# alarm_clock_devkit_esp32.net
KiCad netlist of a schematic drawn in Altium Designer
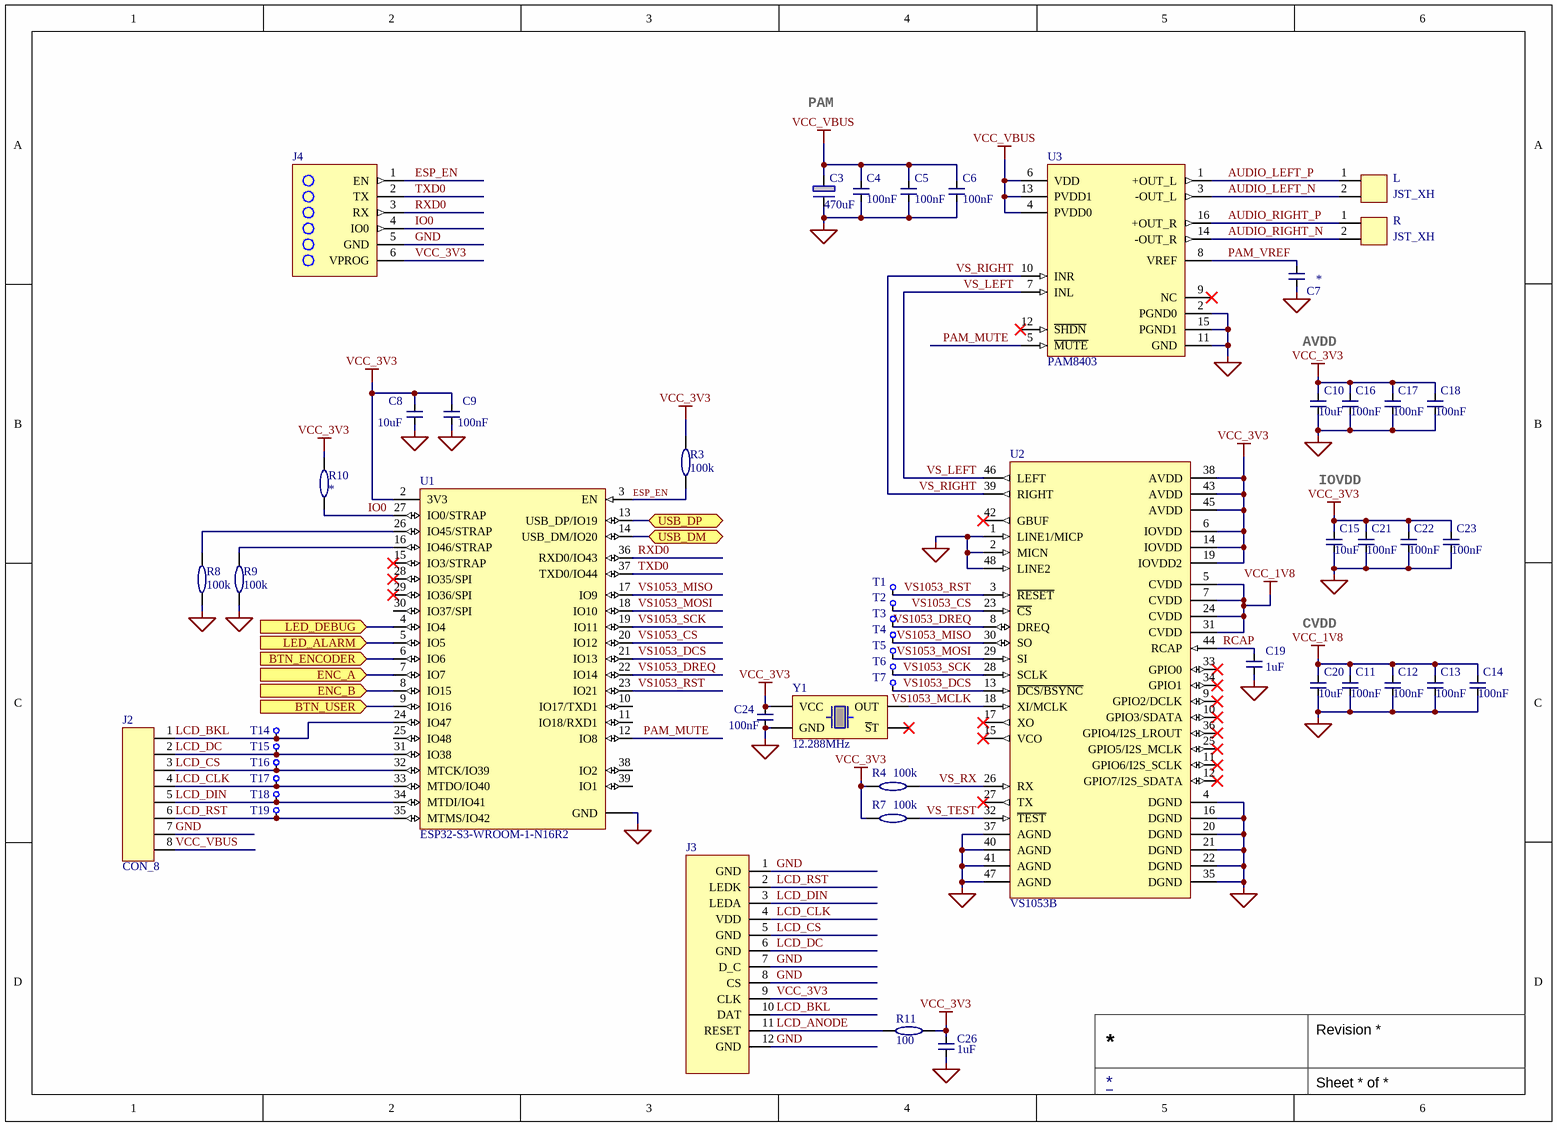
[diagram p0: alarm_clock_devkit_esp32.SchDoc]

(export (version "E")
  (design (tool "Eeschema 10.0.6"))
  (components
    (comp (ref "C3")
      (value "470uF")
      (footprint "CAPMP7343X11L")
      (description "Electrolytic Capacitor")
      (fields (field (name "MPN") "EEFCS1A470R") (field (name "VOLTAGE") "6.3V"))
      (libsource (lib "wifi_alarm_clock") (part "EEFCS1A470R"))
    )
    (comp (ref "C4")
      (value "100nF")
      (footprint "CAP 0603_1608")
      (description "MLCC")
      (libsource (lib "wifi_alarm_clock") (part "CAP_CERAMIC"))
    )
    (comp (ref "C5")
      (value "100nF")
      (footprint "CAP 0603_1608")
      (description "MLCC")
      (libsource (lib "wifi_alarm_clock") (part "CAP_CERAMIC"))
    )
    (comp (ref "C6")
      (value "100nF")
      (footprint "CAP 0603_1608")
      (description "MLCC")
      (libsource (lib "wifi_alarm_clock") (part "CAP_CERAMIC"))
    )
    (comp (ref "C7")
      (value "*")
      (footprint "CAP 0603_1608")
      (description "MLCC")
      (libsource (lib "wifi_alarm_clock") (part "CAP_CERAMIC"))
    )
    (comp (ref "C8")
      (value "10uF")
      (footprint "CAP 1210_3225")
      (description "MLCC")
      (libsource (lib "wifi_alarm_clock") (part "CAP_CERAMIC"))
    )
    (comp (ref "C9")
      (value "100nF")
      (footprint "CAP 0805_2012")
      (description "MLCC")
      (libsource (lib "wifi_alarm_clock") (part "CAP_CERAMIC"))
    )
    (comp (ref "C10")
      (value "10uF")
      (footprint "CAP 1210_3225")
      (description "MLCC")
      (libsource (lib "wifi_alarm_clock") (part "CAP_CERAMIC"))
    )
    (comp (ref "C11")
      (value "100nF")
      (footprint "CAP 0603_1608")
      (description "MLCC")
      (libsource (lib "wifi_alarm_clock") (part "CAP_CERAMIC"))
    )
    (comp (ref "C12")
      (value "100nF")
      (footprint "CAP 0603_1608")
      (description "MLCC")
      (libsource (lib "wifi_alarm_clock") (part "CAP_CERAMIC"))
    )
    (comp (ref "C13")
      (value "100nF")
      (footprint "CAP 0603_1608")
      (description "MLCC")
      (libsource (lib "wifi_alarm_clock") (part "CAP_CERAMIC"))
    )
    (comp (ref "C14")
      (value "100nF")
      (footprint "CAP 0603_1608")
      (description "MLCC")
      (libsource (lib "wifi_alarm_clock") (part "CAP_CERAMIC"))
    )
    (comp (ref "C15")
      (value "10uF")
      (footprint "CAP 1210_3225")
      (description "MLCC")
      (libsource (lib "wifi_alarm_clock") (part "CAP_CERAMIC"))
    )
    (comp (ref "C16")
      (value "100nF")
      (footprint "CAP 0603_1608")
      (description "MLCC")
      (libsource (lib "wifi_alarm_clock") (part "CAP_CERAMIC"))
    )
    (comp (ref "C17")
      (value "100nF")
      (footprint "CAP 0603_1608")
      (description "MLCC")
      (libsource (lib "wifi_alarm_clock") (part "CAP_CERAMIC"))
    )
    (comp (ref "C18")
      (value "100nF")
      (footprint "CAP 0603_1608")
      (description "MLCC")
      (libsource (lib "wifi_alarm_clock") (part "CAP_CERAMIC"))
    )
    (comp (ref "C19")
      (value "1uF")
      (footprint "CAP 0805_2012")
      (description "MLCC")
      (libsource (lib "wifi_alarm_clock") (part "CAP_CERAMIC"))
    )
    (comp (ref "C20")
      (value "10uF")
      (footprint "CAP 1210_3225")
      (description "MLCC")
      (libsource (lib "wifi_alarm_clock") (part "CAP_CERAMIC"))
    )
    (comp (ref "C21")
      (value "100nF")
      (footprint "CAP 0603_1608")
      (description "MLCC")
      (libsource (lib "wifi_alarm_clock") (part "CAP_CERAMIC"))
    )
    (comp (ref "C22")
      (value "100nF")
      (footprint "CAP 0603_1608")
      (description "MLCC")
      (libsource (lib "wifi_alarm_clock") (part "CAP_CERAMIC"))
    )
    (comp (ref "C23")
      (value "100nF")
      (footprint "CAP 0603_1608")
      (description "MLCC")
      (libsource (lib "wifi_alarm_clock") (part "CAP_CERAMIC"))
    )
    (comp (ref "C24")
      (value "100nF")
      (footprint "CAP 0603_1608")
      (description "MLCC")
      (libsource (lib "wifi_alarm_clock") (part "CAP_CERAMIC"))
    )
    (comp (ref "C26")
      (value "1uF")
      (footprint "CAP 0805_2012")
      (description "MLCC")
      (libsource (lib "wifi_alarm_clock") (part "CAP_CERAMIC"))
    )
    (comp (ref "J2") (value "CON_8") (footprint "CON8") (libsource (lib "wifi_alarm_clock") (part "CON_8")))
    (comp (ref "J3")
      (value "LCD_CON12")
      (footprint "LCD_CON12")
      (libsource (lib "wifi_alarm_clock") (part "LCD_CON12"))
    )
    (comp (ref "J4")
      (value "ESP_PROG")
      (footprint "ESP_PROG")
      (libsource (lib "wifi_alarm_clock") (part "ESP_PROG"))
    )
    (comp (ref "L")
      (value "JST_XH")
      (footprint "JST_XH_x2")
      (libsource (lib "wifi_alarm_clock") (part "JST_XH"))
    )
    (comp (ref "R")
      (value "JST_XH")
      (footprint "JST_XH_x2")
      (libsource (lib "wifi_alarm_clock") (part "JST_XH"))
    )
    (comp (ref "R3")
      (value "100k")
      (footprint "RES 0603_1608")
      (description "Resistor")
      (libsource (lib "wifi_alarm_clock") (part "RESISTOR"))
    )
    (comp (ref "R4")
      (value "100k")
      (footprint "RES 0603_1608")
      (description "Resistor")
      (libsource (lib "wifi_alarm_clock") (part "RESISTOR"))
    )
    (comp (ref "R7")
      (value "100k")
      (footprint "RES 0603_1608")
      (description "Resistor")
      (libsource (lib "wifi_alarm_clock") (part "RESISTOR"))
    )
    (comp (ref "R8")
      (value "100k")
      (footprint "RES 0603_1608")
      (description "Resistor")
      (libsource (lib "wifi_alarm_clock") (part "RESISTOR"))
    )
    (comp (ref "R9")
      (value "100k")
      (footprint "RES 0603_1608")
      (description "Resistor")
      (libsource (lib "wifi_alarm_clock") (part "RESISTOR"))
    )
    (comp (ref "R10")
      (value "*")
      (footprint "RES 0603_1608")
      (description "Resistor")
      (libsource (lib "wifi_alarm_clock") (part "RESISTOR"))
    )
    (comp (ref "R11")
      (value "100")
      (footprint "RES 0603_1608")
      (description "Resistor")
      (libsource (lib "wifi_alarm_clock") (part "RESISTOR"))
    )
    (comp (ref "T1")
      (value "TESTPOINT")
      (footprint "TESTPOINT_1MM")
      (libsource (lib "wifi_alarm_clock") (part "TESTPOINT"))
    )
    (comp (ref "T2")
      (value "TESTPOINT")
      (footprint "TESTPOINT_1MM")
      (libsource (lib "wifi_alarm_clock") (part "TESTPOINT"))
    )
    (comp (ref "T3")
      (value "TESTPOINT")
      (footprint "TESTPOINT_1MM")
      (libsource (lib "wifi_alarm_clock") (part "TESTPOINT"))
    )
    (comp (ref "T4")
      (value "TESTPOINT")
      (footprint "TESTPOINT_1MM")
      (libsource (lib "wifi_alarm_clock") (part "TESTPOINT"))
    )
    (comp (ref "T5")
      (value "TESTPOINT")
      (footprint "TESTPOINT_1MM")
      (libsource (lib "wifi_alarm_clock") (part "TESTPOINT"))
    )
    (comp (ref "T6")
      (value "TESTPOINT")
      (footprint "TESTPOINT_1MM")
      (libsource (lib "wifi_alarm_clock") (part "TESTPOINT"))
    )
    (comp (ref "T7")
      (value "TESTPOINT")
      (footprint "TESTPOINT_1MM")
      (libsource (lib "wifi_alarm_clock") (part "TESTPOINT"))
    )
    (comp (ref "T14")
      (value "TESTPOINT")
      (footprint "TESTPOINT_1MM")
      (libsource (lib "wifi_alarm_clock") (part "TESTPOINT"))
    )
    (comp (ref "T15")
      (value "TESTPOINT")
      (footprint "TESTPOINT_1MM")
      (libsource (lib "wifi_alarm_clock") (part "TESTPOINT"))
    )
    (comp (ref "T16")
      (value "TESTPOINT")
      (footprint "TESTPOINT_1MM")
      (libsource (lib "wifi_alarm_clock") (part "TESTPOINT"))
    )
    (comp (ref "T17")
      (value "TESTPOINT")
      (footprint "TESTPOINT_1MM")
      (libsource (lib "wifi_alarm_clock") (part "TESTPOINT"))
    )
    (comp (ref "T18")
      (value "TESTPOINT")
      (footprint "TESTPOINT_1MM")
      (libsource (lib "wifi_alarm_clock") (part "TESTPOINT"))
    )
    (comp (ref "T19")
      (value "TESTPOINT")
      (footprint "TESTPOINT_1MM")
      (libsource (lib "wifi_alarm_clock") (part "TESTPOINT"))
    )
    (comp (ref "U1")
      (value "ESP32-S3-WROOM-1-N16R2")
      (footprint "XCVR_ESP32-S3-WROOM-1-N16R2")
      (description "Bluetooth, WiFi 802.11b/g/n, Bluetooth v5.0 Transceiver Module 2.4GHz PCB Trace Surface Mount")
      (fields (field (name "MF") "Espressif Systems") (field (name "MP") "ESP32S3WROOM1N16R2"))
      (libsource (lib "wifi_alarm_clock") (part "ESP32-S3-WROOM-1-N16R2"))
    )
    (comp (ref "U2")
      (value "VS1053B")
      (footprint "CQFP50P900X900X140-48N")
      (description "VS1053B Music Maker Audio Feather Platform Evaluation Expansion Board")
      (fields (field (name "MF") "SparkFun Electronics"))
      (libsource (lib "wifi_alarm_clock") (part "VS1053B"))
    )
    (comp (ref "U3")
      (value "PAM8403")
      (footprint "SOIC127P600X175-16N")
      (description "Audio Amp Speaker 2-CH Stereo 3.2W Class-D 16-Pin SOP T/R")
      (fields (field (name "MF") "Diodes Zetex"))
      (libsource (lib "wifi_alarm_clock") (part "PAM8403"))
    )
    (comp (ref "Y1")
      (value "12.288MHz")
      (footprint "NDK NX3225GA")
      (description "SMT Crystal")
      (libsource (lib "wifi_alarm_clock") (part "OSCILLATOR"))
    )
  )
  (nets
    (net (code "1") (name "/AUDIO_LEFT_N") (class "Default")
      (node (ref "L") (pin "2") (pinfunction "2_2") (pintype "passive"))
      (node (ref "U3") (pin "3") (pinfunction "-OUT_L_3") (pintype "output"))
    )
    (net (code "2") (name "/AUDIO_LEFT_P") (class "Default")
      (node (ref "L") (pin "1") (pinfunction "1_1") (pintype "passive"))
      (node (ref "U3") (pin "1") (pinfunction "+OUT_L_1") (pintype "output"))
    )
    (net (code "3") (name "/AUDIO_RIGHT_N") (class "Default")
      (node (ref "R") (pin "2") (pinfunction "2_2") (pintype "passive"))
      (node (ref "U3") (pin "14") (pinfunction "-OUT_R_14") (pintype "output"))
    )
    (net (code "4") (name "/AUDIO_RIGHT_P") (class "Default")
      (node (ref "R") (pin "1") (pinfunction "1_1") (pintype "passive"))
      (node (ref "U3") (pin "16") (pinfunction "+OUT_R_16") (pintype "output"))
    )
    (net (code "5") (name "/BTN_ENCODER") (class "Default")
      (node (ref "U1") (pin "6") (pinfunction "IO6_6") (pintype "bidirectional"))
    )
    (net (code "6") (name "/BTN_USER") (class "Default")
      (node (ref "U1") (pin "9") (pinfunction "IO16_9") (pintype "bidirectional"))
    )
    (net (code "7") (name "/ENC_A") (class "Default")
      (node (ref "U1") (pin "7") (pinfunction "IO7_7") (pintype "bidirectional"))
    )
    (net (code "8") (name "/ENC_B") (class "Default")
      (node (ref "U1") (pin "8") (pinfunction "IO15_8") (pintype "bidirectional"))
    )
    (net (code "9") (name "/ESP_EN") (class "Default")
      (node (ref "J4") (pin "1") (pinfunction "EN_1") (pintype "output"))
      (node (ref "R3") (pin "1") (pinfunction "A_1") (pintype "passive"))
      (node (ref "U1") (pin "3") (pinfunction "EN_3") (pintype "input"))
    )
    (net (code "10") (name "/IO0") (class "Default")
      (node (ref "J4") (pin "4") (pinfunction "IO0_4") (pintype "output"))
      (node (ref "R10") (pin "2") (pinfunction "B_2") (pintype "passive"))
      (node (ref "U1") (pin "27") (pinfunction "IO0/STRAP_27") (pintype "bidirectional"))
    )
    (net (code "11") (name "/LCD_ANODE") (class "Default")
      (node (ref "J3") (pin "11") (pinfunction "RESET_11") (pintype "passive"))
      (node (ref "R11") (pin "1") (pinfunction "A_1") (pintype "passive"))
    )
    (net (code "12") (name "/LCD_BKL") (class "Default")
      (node (ref "J2") (pin "1") (pinfunction "1_1") (pintype "passive"))
      (node (ref "J3") (pin "10") (pinfunction "DAT_10") (pintype "passive"))
      (node (ref "T14") (pin "1") (pintype "passive"))
      (node (ref "U1") (pin "24") (pinfunction "IO47_24") (pintype "bidirectional"))
    )
    (net (code "13") (name "/LCD_CLK") (class "Default")
      (node (ref "J2") (pin "4") (pinfunction "4_4") (pintype "passive"))
      (node (ref "J3") (pin "4") (pinfunction "VDD_4") (pintype "passive"))
      (node (ref "T17") (pin "1") (pintype "passive"))
      (node (ref "U1") (pin "33") (pinfunction "MTDO/IO40_33") (pintype "bidirectional"))
    )
    (net (code "14") (name "/LCD_CS") (class "Default")
      (node (ref "J2") (pin "3") (pinfunction "3_3") (pintype "passive"))
      (node (ref "J3") (pin "5") (pinfunction "GND_5") (pintype "passive"))
      (node (ref "T16") (pin "1") (pintype "passive"))
      (node (ref "U1") (pin "32") (pinfunction "MTCK/IO39_32") (pintype "bidirectional"))
    )
    (net (code "15") (name "/LCD_DC") (class "Default")
      (node (ref "J2") (pin "2") (pinfunction "2_2") (pintype "passive"))
      (node (ref "J3") (pin "6") (pinfunction "GND_6") (pintype "passive"))
      (node (ref "T15") (pin "1") (pintype "passive"))
      (node (ref "U1") (pin "31") (pinfunction "IO38_31") (pintype "bidirectional"))
    )
    (net (code "16") (name "/LCD_DIN") (class "Default")
      (node (ref "J2") (pin "5") (pinfunction "5_5") (pintype "passive"))
      (node (ref "J3") (pin "3") (pinfunction "LEDA_3") (pintype "passive"))
      (node (ref "T18") (pin "1") (pintype "passive"))
      (node (ref "U1") (pin "34") (pinfunction "MTDI/IO41_34") (pintype "bidirectional"))
    )
    (net (code "17") (name "/LCD_RST") (class "Default")
      (node (ref "J2") (pin "6") (pinfunction "6_6") (pintype "passive"))
      (node (ref "J3") (pin "2") (pinfunction "LEDK_2") (pintype "passive"))
      (node (ref "T19") (pin "1") (pintype "passive"))
      (node (ref "U1") (pin "35") (pinfunction "MTMS/IO42_35") (pintype "bidirectional"))
    )
    (net (code "18") (name "/LED_ALARM") (class "Default")
      (node (ref "U1") (pin "5") (pinfunction "IO5_5") (pintype "bidirectional"))
    )
    (net (code "19") (name "/LED_DEBUG") (class "Default")
      (node (ref "U1") (pin "4") (pinfunction "IO4_4") (pintype "bidirectional"))
    )
    (net (code "20") (name "/PAM_MUTE") (class "Default")
      (node (ref "U1") (pin "12") (pinfunction "IO8_12") (pintype "bidirectional"))
      (node (ref "U3") (pin "5") (pinfunction "~{MUTE}_5") (pintype "input"))
    )
    (net (code "21") (name "/PAM_VREF") (class "Default")
      (node (ref "C7") (pin "2") (pinfunction "B_2") (pintype "passive"))
      (node (ref "U3") (pin "8") (pinfunction "VREF_8") (pintype "passive"))
    )
    (net (code "22") (name "/RCAP") (class "Default")
      (node (ref "C19") (pin "2") (pinfunction "B_2") (pintype "passive"))
      (node (ref "U2") (pin "44") (pinfunction "RCAP_44") (pintype "input"))
    )
    (net (code "23") (name "/RXD0") (class "Default")
      (node (ref "J4") (pin "3") (pinfunction "RX_3") (pintype "output"))
      (node (ref "U1") (pin "36") (pinfunction "RXD0/IO43_36") (pintype "bidirectional"))
    )
    (net (code "24") (name "/TXD0") (class "Default")
      (node (ref "J4") (pin "2") (pinfunction "TX_2") (pintype "passive"))
      (node (ref "U1") (pin "37") (pinfunction "TXD0/IO44_37") (pintype "bidirectional"))
    )
    (net (code "25") (name "/USB_DM") (class "Default")
      (node (ref "U1") (pin "14") (pinfunction "USB_DM/IO20_14") (pintype "bidirectional"))
    )
    (net (code "26") (name "/USB_DP") (class "Default")
      (node (ref "U1") (pin "13") (pinfunction "USB_DP/IO19_13") (pintype "bidirectional"))
    )
    (net (code "27") (name "/VS1053_CS") (class "Default")
      (node (ref "T2") (pin "1") (pintype "passive"))
      (node (ref "U1") (pin "20") (pinfunction "IO12_20") (pintype "bidirectional"))
      (node (ref "U2") (pin "23") (pinfunction "~{CS}_23") (pintype "input"))
    )
    (net (code "28") (name "/VS1053_DCS") (class "Default")
      (node (ref "T7") (pin "1") (pintype "passive"))
      (node (ref "U1") (pin "21") (pinfunction "IO13_21") (pintype "bidirectional"))
      (node (ref "U2") (pin "13") (pinfunction "~{DCS/BSYNC}_13") (pintype "input"))
    )
    (net (code "29") (name "/VS1053_DREQ") (class "Default")
      (node (ref "T3") (pin "1") (pintype "passive"))
      (node (ref "U1") (pin "22") (pinfunction "IO14_22") (pintype "bidirectional"))
      (node (ref "U2") (pin "8") (pinfunction "DREQ_8") (pintype "bidirectional"))
    )
    (net (code "30") (name "/VS1053_MCLK") (class "Default")
      (node (ref "U2") (pin "18") (pinfunction "XI/MCLK_18") (pintype "input"))
      (node (ref "Y1") (pin "3") (pinfunction "OUT_3") (pintype "passive"))
    )
    (net (code "31") (name "/VS1053_MISO") (class "Default")
      (node (ref "T4") (pin "1") (pintype "passive"))
      (node (ref "U1") (pin "17") (pinfunction "IO9_17") (pintype "bidirectional"))
      (node (ref "U2") (pin "30") (pinfunction "SO_30") (pintype "bidirectional"))
    )
    (net (code "32") (name "/VS1053_MOSI") (class "Default")
      (node (ref "T5") (pin "1") (pintype "passive"))
      (node (ref "U1") (pin "18") (pinfunction "IO10_18") (pintype "bidirectional"))
      (node (ref "U2") (pin "29") (pinfunction "SI_29") (pintype "input"))
    )
    (net (code "33") (name "/VS1053_RST") (class "Default")
      (node (ref "T1") (pin "1") (pintype "passive"))
      (node (ref "U1") (pin "23") (pinfunction "IO21_23") (pintype "bidirectional"))
      (node (ref "U2") (pin "3") (pinfunction "~{RESET}_3") (pintype "input"))
    )
    (net (code "34") (name "/VS1053_SCK") (class "Default")
      (node (ref "T6") (pin "1") (pintype "passive"))
      (node (ref "U1") (pin "19") (pinfunction "IO11_19") (pintype "bidirectional"))
      (node (ref "U2") (pin "28") (pinfunction "SCLK_28") (pintype "input"))
    )
    (net (code "35") (name "/VS_LEFT") (class "Default")
      (node (ref "U2") (pin "46") (pinfunction "LEFT_46") (pintype "output"))
      (node (ref "U3") (pin "7") (pinfunction "INL_7") (pintype "input"))
    )
    (net (code "36") (name "/VS_RIGHT") (class "Default")
      (node (ref "U2") (pin "39") (pinfunction "RIGHT_39") (pintype "output"))
      (node (ref "U3") (pin "10") (pinfunction "INR_10") (pintype "input"))
    )
    (net (code "37") (name "/VS_RX") (class "Default")
      (node (ref "R4") (pin "2") (pinfunction "B_2") (pintype "passive"))
      (node (ref "U2") (pin "26") (pinfunction "RX_26") (pintype "input"))
    )
    (net (code "38") (name "/VS_TEST") (class "Default")
      (node (ref "R7") (pin "2") (pinfunction "B_2") (pintype "passive"))
      (node (ref "U2") (pin "32") (pinfunction "~{TEST}_32") (pintype "input"))
    )
    (net (code "39") (name "GND") (class "Default")
      (node (ref "C10") (pin "1") (pinfunction "A_1") (pintype "passive"))
      (node (ref "C11") (pin "1") (pinfunction "A_1") (pintype "passive"))
      (node (ref "C12") (pin "1") (pinfunction "A_1") (pintype "passive"))
      (node (ref "C13") (pin "1") (pinfunction "A_1") (pintype "passive"))
      (node (ref "C14") (pin "1") (pinfunction "A_1") (pintype "passive"))
      (node (ref "C15") (pin "1") (pinfunction "A_1") (pintype "passive"))
      (node (ref "C16") (pin "1") (pinfunction "A_1") (pintype "passive"))
      (node (ref "C17") (pin "1") (pinfunction "A_1") (pintype "passive"))
      (node (ref "C18") (pin "1") (pinfunction "A_1") (pintype "passive"))
      (node (ref "C19") (pin "1") (pinfunction "A_1") (pintype "passive"))
      (node (ref "C20") (pin "1") (pinfunction "A_1") (pintype "passive"))
      (node (ref "C21") (pin "1") (pinfunction "A_1") (pintype "passive"))
      (node (ref "C22") (pin "1") (pinfunction "A_1") (pintype "passive"))
      (node (ref "C23") (pin "1") (pinfunction "A_1") (pintype "passive"))
      (node (ref "C24") (pin "1") (pinfunction "A_1") (pintype "passive"))
      (node (ref "C26") (pin "1") (pinfunction "A_1") (pintype "passive"))
      (node (ref "C3") (pin "2") (pinfunction "-_2") (pintype "passive"))
      (node (ref "C4") (pin "1") (pinfunction "A_1") (pintype "passive"))
      (node (ref "C5") (pin "1") (pinfunction "A_1") (pintype "passive"))
      (node (ref "C6") (pin "1") (pinfunction "A_1") (pintype "passive"))
      (node (ref "C7") (pin "1") (pinfunction "A_1") (pintype "passive"))
      (node (ref "C8") (pin "1") (pinfunction "A_1") (pintype "passive"))
      (node (ref "C9") (pin "1") (pinfunction "A_1") (pintype "passive"))
      (node (ref "J2") (pin "7") (pinfunction "7_7") (pintype "passive"))
      (node (ref "J3") (pin "1") (pinfunction "GND_1") (pintype "passive"))
      (node (ref "J3") (pin "12") (pinfunction "GND_12") (pintype "passive"))
      (node (ref "J3") (pin "7") (pinfunction "D_C_7") (pintype "passive"))
      (node (ref "J3") (pin "8") (pinfunction "CS_8") (pintype "passive"))
      (node (ref "J4") (pin "5") (pinfunction "GND_5") (pintype "passive"))
      (node (ref "R8") (pin "2") (pinfunction "B_2") (pintype "passive"))
      (node (ref "R9") (pin "1") (pinfunction "A_1") (pintype "passive"))
      (node (ref "U1") (pin "GND") (pinfunction "GND_GND") (pintype "power_in"))
      (node (ref "U2") (pin "1") (pinfunction "LINE1/MICP_1") (pintype "input"))
      (node (ref "U2") (pin "16") (pinfunction "DGND_16") (pintype "power_in"))
      (node (ref "U2") (pin "2") (pinfunction "MICN_2") (pintype "input"))
      (node (ref "U2") (pin "20") (pinfunction "DGND_20") (pintype "power_in"))
      (node (ref "U2") (pin "21") (pinfunction "DGND_21") (pintype "power_in"))
      (node (ref "U2") (pin "22") (pinfunction "DGND_22") (pintype "power_in"))
      (node (ref "U2") (pin "35") (pinfunction "DGND_35") (pintype "power_in"))
      (node (ref "U2") (pin "37") (pinfunction "AGND_37") (pintype "power_in"))
      (node (ref "U2") (pin "4") (pinfunction "DGND_4") (pintype "power_in"))
      (node (ref "U2") (pin "40") (pinfunction "AGND_40") (pintype "power_in"))
      (node (ref "U2") (pin "41") (pinfunction "AGND_41") (pintype "power_in"))
      (node (ref "U2") (pin "47") (pinfunction "AGND_47") (pintype "power_in"))
      (node (ref "U2") (pin "48") (pinfunction "LINE2_48") (pintype "input"))
      (node (ref "U3") (pin "11") (pinfunction "GND_11") (pintype "power_in"))
      (node (ref "U3") (pin "15") (pinfunction "PGND1_15") (pintype "power_in"))
      (node (ref "U3") (pin "2") (pinfunction "PGND0_2") (pintype "power_in"))
      (node (ref "Y1") (pin "2") (pinfunction "GND_2") (pintype "passive"))
    )
    (net (code "40") (name "Net-(R8-A)") (class "Default")
      (node (ref "R8") (pin "1") (pinfunction "A_1") (pintype "passive"))
      (node (ref "U1") (pin "26") (pinfunction "IO45/STRAP_26") (pintype "bidirectional"))
    )
    (net (code "41") (name "Net-(R9-B)") (class "Default")
      (node (ref "R9") (pin "2") (pinfunction "B_2") (pintype "passive"))
      (node (ref "U1") (pin "16") (pinfunction "IO46/STRAP_16") (pintype "bidirectional"))
    )
    (net (code "42") (name "VCC_1V8") (class "Default")
      (node (ref "C11") (pin "2") (pinfunction "B_2") (pintype "passive"))
      (node (ref "C12") (pin "2") (pinfunction "B_2") (pintype "passive"))
      (node (ref "C13") (pin "2") (pinfunction "B_2") (pintype "passive"))
      (node (ref "C14") (pin "2") (pinfunction "B_2") (pintype "passive"))
      (node (ref "C20") (pin "2") (pinfunction "B_2") (pintype "passive"))
      (node (ref "U2") (pin "24") (pinfunction "CVDD_24") (pintype "power_in"))
      (node (ref "U2") (pin "31") (pinfunction "CVDD_31") (pintype "power_in"))
      (node (ref "U2") (pin "5") (pinfunction "CVDD_5") (pintype "power_in"))
      (node (ref "U2") (pin "7") (pinfunction "CVDD_7") (pintype "power_in"))
    )
    (net (code "43") (name "VCC_3V3") (class "Default")
      (node (ref "C10") (pin "2") (pinfunction "B_2") (pintype "passive"))
      (node (ref "C15") (pin "2") (pinfunction "B_2") (pintype "passive"))
      (node (ref "C16") (pin "2") (pinfunction "B_2") (pintype "passive"))
      (node (ref "C17") (pin "2") (pinfunction "B_2") (pintype "passive"))
      (node (ref "C18") (pin "2") (pinfunction "B_2") (pintype "passive"))
      (node (ref "C21") (pin "2") (pinfunction "B_2") (pintype "passive"))
      (node (ref "C22") (pin "2") (pinfunction "B_2") (pintype "passive"))
      (node (ref "C23") (pin "2") (pinfunction "B_2") (pintype "passive"))
      (node (ref "C24") (pin "2") (pinfunction "B_2") (pintype "passive"))
      (node (ref "C26") (pin "2") (pinfunction "B_2") (pintype "passive"))
      (node (ref "C8") (pin "2") (pinfunction "B_2") (pintype "passive"))
      (node (ref "C9") (pin "2") (pinfunction "B_2") (pintype "passive"))
      (node (ref "J3") (pin "9") (pinfunction "CLK_9") (pintype "passive"))
      (node (ref "J4") (pin "6") (pinfunction "VPROG_6") (pintype "passive"))
      (node (ref "R10") (pin "1") (pinfunction "A_1") (pintype "passive"))
      (node (ref "R11") (pin "2") (pinfunction "B_2") (pintype "passive"))
      (node (ref "R3") (pin "2") (pinfunction "B_2") (pintype "passive"))
      (node (ref "R4") (pin "1") (pinfunction "A_1") (pintype "passive"))
      (node (ref "R7") (pin "1") (pinfunction "A_1") (pintype "passive"))
      (node (ref "U1") (pin "2") (pinfunction "3V3_2") (pintype "power_in"))
      (node (ref "U2") (pin "14") (pinfunction "IOVDD_14") (pintype "power_in"))
      (node (ref "U2") (pin "19") (pinfunction "IOVDD2_19") (pintype "power_in"))
      (node (ref "U2") (pin "38") (pinfunction "AVDD_38") (pintype "power_in"))
      (node (ref "U2") (pin "43") (pinfunction "AVDD_43") (pintype "power_in"))
      (node (ref "U2") (pin "45") (pinfunction "AVDD_45") (pintype "power_in"))
      (node (ref "U2") (pin "6") (pinfunction "IOVDD_6") (pintype "power_in"))
      (node (ref "Y1") (pin "4") (pinfunction "VCC_4") (pintype "passive"))
    )
    (net (code "44") (name "VCC_VBUS") (class "Default")
      (node (ref "C3") (pin "1") (pinfunction "+_1") (pintype "passive"))
      (node (ref "C4") (pin "2") (pinfunction "B_2") (pintype "passive"))
      (node (ref "C5") (pin "2") (pinfunction "B_2") (pintype "passive"))
      (node (ref "C6") (pin "2") (pinfunction "B_2") (pintype "passive"))
      (node (ref "J2") (pin "8") (pinfunction "8_8") (pintype "passive"))
      (node (ref "U3") (pin "13") (pinfunction "PVDD1_13") (pintype "power_in"))
      (node (ref "U3") (pin "4") (pinfunction "PVDD0_4") (pintype "power_in"))
      (node (ref "U3") (pin "6") (pinfunction "VDD_6") (pintype "power_in"))
    )
    (net (code "45") (name "unconnected-(U1-IO1-Pad39)") (class "Default")
      (node (ref "U1") (pin "39") (pinfunction "IO1_39") (pintype "bidirectional"))
    )
    (net (code "46") (name "unconnected-(U1-IO2-Pad38)") (class "Default")
      (node (ref "U1") (pin "38") (pinfunction "IO2_38") (pintype "bidirectional"))
    )
    (net (code "47") (name "unconnected-(U1-IO3{slash}STRAP-Pad15)") (class "Default")
      (node (ref "U1") (pin "15") (pinfunction "IO3/STRAP_15") (pintype "bidirectional+no_connect"))
    )
    (net (code "48") (name "unconnected-(U1-IO17{slash}TXD1-Pad10)") (class "Default")
      (node (ref "U1") (pin "10") (pinfunction "IO17/TXD1_10") (pintype "bidirectional"))
    )
    (net (code "49") (name "unconnected-(U1-IO18{slash}RXD1-Pad11)") (class "Default")
      (node (ref "U1") (pin "11") (pinfunction "IO18/RXD1_11") (pintype "bidirectional"))
    )
    (net (code "50") (name "unconnected-(U1-IO35{slash}SPI-Pad28)") (class "Default")
      (node (ref "U1") (pin "28") (pinfunction "IO35/SPI_28") (pintype "bidirectional+no_connect"))
    )
    (net (code "51") (name "unconnected-(U1-IO36{slash}SPI-Pad29)") (class "Default")
      (node (ref "U1") (pin "29") (pinfunction "IO36/SPI_29") (pintype "bidirectional+no_connect"))
    )
    (net (code "52") (name "unconnected-(U1-IO37{slash}SPI-Pad30)") (class "Default")
      (node (ref "U1") (pin "30") (pinfunction "IO37/SPI_30") (pintype "bidirectional"))
    )
    (net (code "53") (name "unconnected-(U1-IO48-Pad25)") (class "Default")
      (node (ref "U1") (pin "25") (pinfunction "IO48_25") (pintype "bidirectional"))
    )
    (net (code "54") (name "unconnected-(U2-GBUF-Pad42)") (class "Default")
      (node (ref "U2") (pin "42") (pinfunction "GBUF_42") (pintype "output+no_connect"))
    )
    (net (code "55") (name "unconnected-(U2-GPIO0-Pad33)") (class "Default")
      (node (ref "U2") (pin "33") (pinfunction "GPIO0_33") (pintype "bidirectional+no_connect"))
    )
    (net (code "56") (name "unconnected-(U2-GPIO1-Pad34)") (class "Default")
      (node (ref "U2") (pin "34") (pinfunction "GPIO1_34") (pintype "bidirectional+no_connect"))
    )
    (net (code "57") (name "unconnected-(U2-GPIO2{slash}DCLK-Pad9)") (class "Default")
      (node (ref "U2") (pin "9") (pinfunction "GPIO2/DCLK_9") (pintype "bidirectional+no_connect"))
    )
    (net (code "58") (name "unconnected-(U2-GPIO3{slash}SDATA-Pad10)") (class "Default")
      (node (ref "U2") (pin "10") (pinfunction "GPIO3/SDATA_10") (pintype "bidirectional+no_connect"))
    )
    (net (code "59") (name "unconnected-(U2-GPIO4{slash}I2S_LROUT-Pad36)") (class "Default")
      (node (ref "U2") (pin "36") (pinfunction "GPIO4/I2S_LROUT_36") (pintype "bidirectional+no_connect"))
    )
    (net (code "60") (name "unconnected-(U2-GPIO5{slash}I2S_MCLK-Pad25)") (class "Default")
      (node (ref "U2") (pin "25") (pinfunction "GPIO5/I2S_MCLK_25") (pintype "bidirectional+no_connect"))
    )
    (net (code "61") (name "unconnected-(U2-GPIO6{slash}I2S_SCLK-Pad11)") (class "Default")
      (node (ref "U2") (pin "11") (pinfunction "GPIO6/I2S_SCLK_11") (pintype "bidirectional+no_connect"))
    )
    (net (code "62") (name "unconnected-(U2-GPIO7{slash}I2S_SDATA-Pad12)") (class "Default")
      (node (ref "U2") (pin "12") (pinfunction "GPIO7/I2S_SDATA_12") (pintype "bidirectional+no_connect"))
    )
    (net (code "63") (name "unconnected-(U2-TX-Pad27)") (class "Default")
      (node (ref "U2") (pin "27") (pinfunction "TX_27") (pintype "output+no_connect"))
    )
    (net (code "64") (name "unconnected-(U2-VCO-Pad15)") (class "Default")
      (node (ref "U2") (pin "15") (pinfunction "VCO_15") (pintype "output+no_connect"))
    )
    (net (code "65") (name "unconnected-(U2-XO-Pad17)") (class "Default")
      (node (ref "U2") (pin "17") (pinfunction "XO_17") (pintype "output+no_connect"))
    )
    (net (code "66") (name "unconnected-(U3-NC-Pad9)") (class "Default")
      (node (ref "U3") (pin "9") (pinfunction "NC_9") (pintype "passive+no_connect"))
    )
    (net (code "67") (name "unconnected-(U3-~{SHDN}-Pad12)") (class "Default")
      (node (ref "U3") (pin "12") (pinfunction "~{SHDN}_12") (pintype "input+no_connect"))
    )
    (net (code "68") (name "unconnected-(Y1-~{S}T-Pad1)") (class "Default")
      (node (ref "Y1") (pin "1") (pinfunction "~{S}T_1") (pintype "passive+no_connect"))
    )
  )
)
